# FTDI_Basic-5V.net
KiCad netlist of a schematic drawn in EAGLE
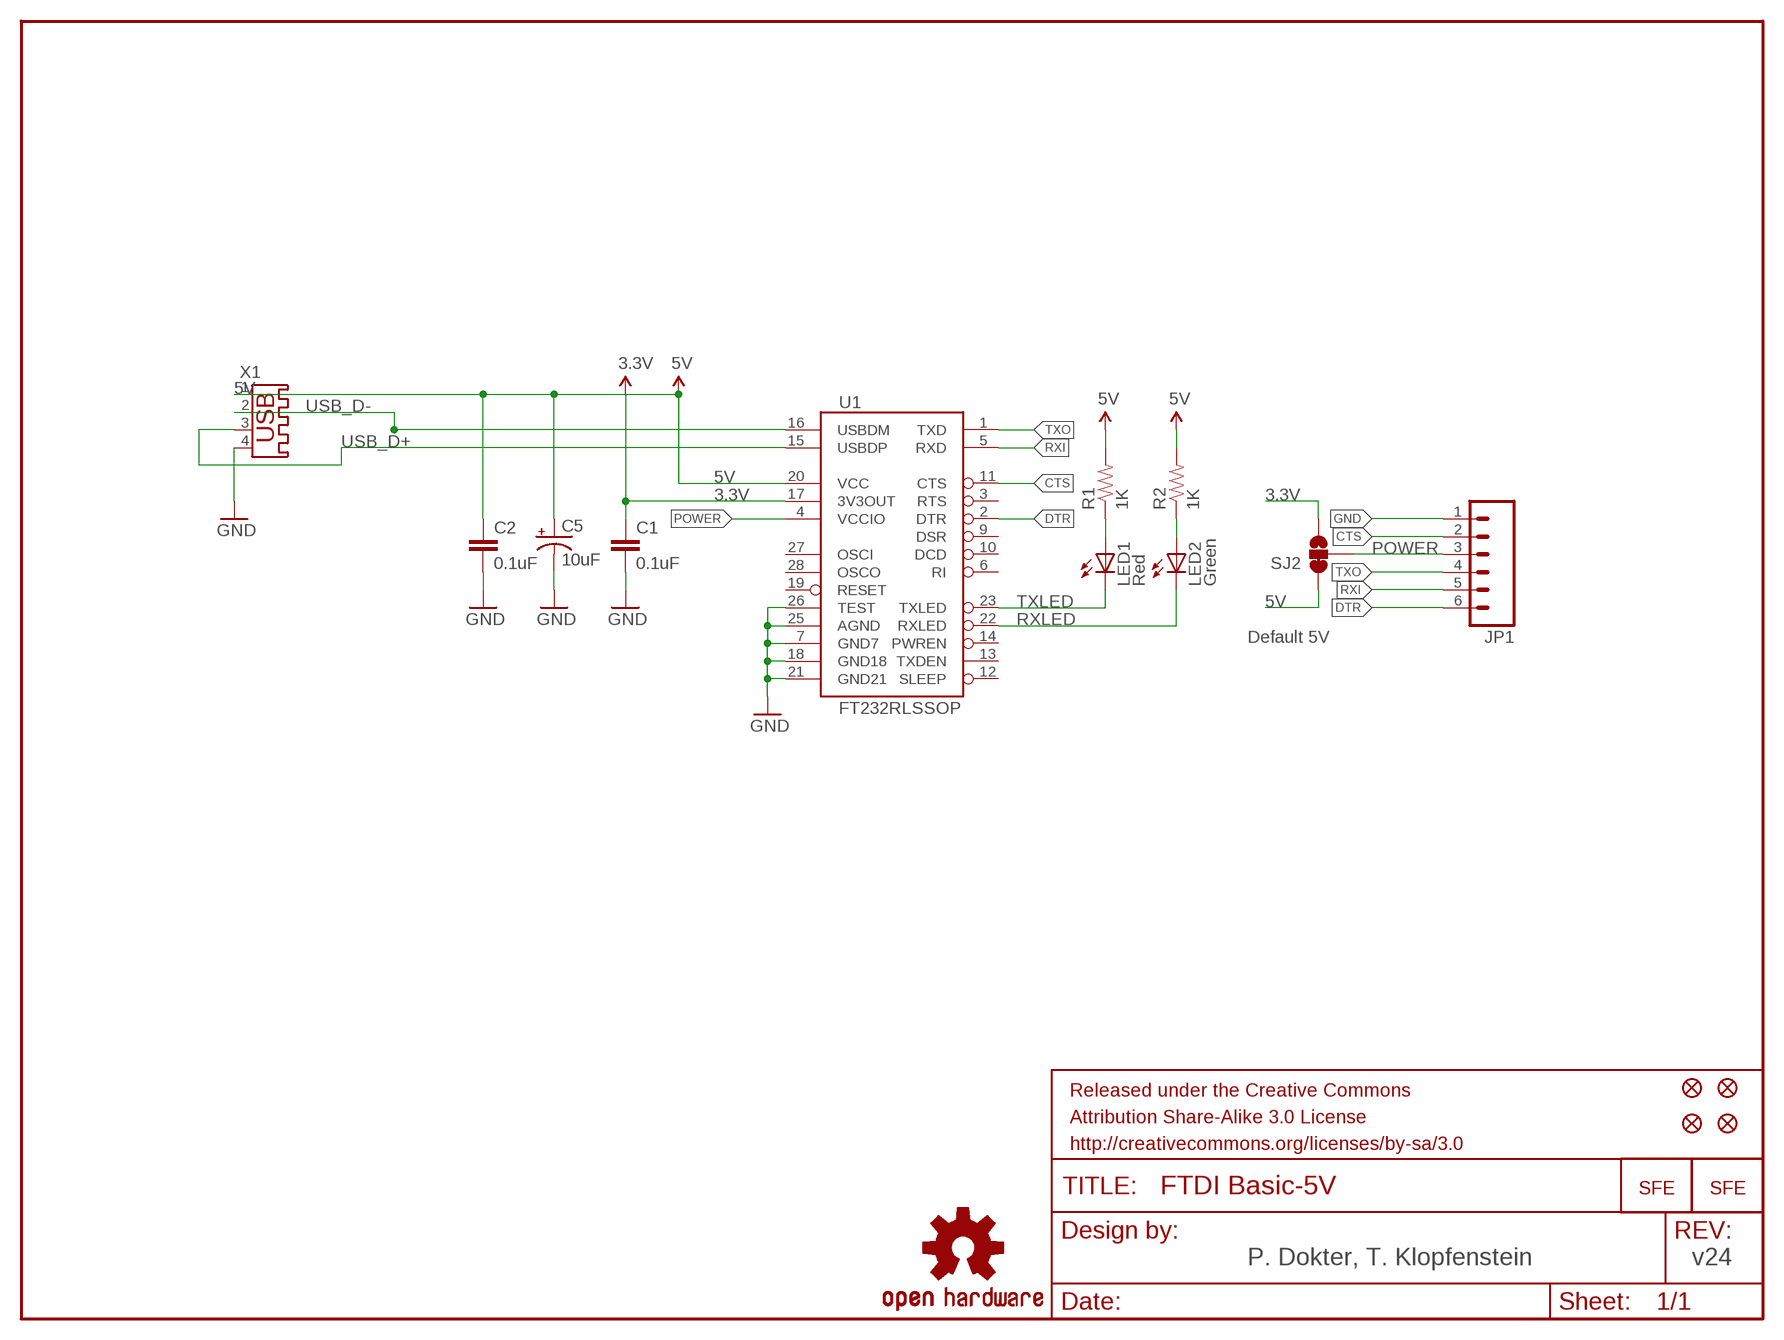
[diagram p0: schematic, sheet 1]

(export (version "E")
  (design (tool "Eeschema 10.0.6"))
  (components
    (comp (ref "C1")
      (value "0.1uF")
      (footprint "eagle-import:0603-CAP")
      (libsource (lib "eagle-import") (part "CAP0603-CAP"))
    )
    (comp (ref "C2")
      (value "0.1uF")
      (footprint "eagle-import:0603-CAP")
      (libsource (lib "eagle-import") (part "CAP0603-CAP"))
    )
    (comp (ref "C5")
      (value "10uF")
      (footprint "eagle-import:EIA3216")
      (libsource (lib "eagle-import") (part "CAP_POL1206"))
    )
    (comp (ref "FRAME1")
      (value "FRAME-LETTER")
      (footprint "eagle-import:CREATIVE_COMMONS")
      (libsource (lib "eagle-import") (part "FRAME-LETTER"))
    )
    (comp (ref "JP1")
      (value "M06SMD-FEMALE-V2")
      (footprint "eagle-import:1X06-SMD-FEMALE-V2")
      (libsource (lib "eagle-import") (part "M06SMD-FEMALE-V2"))
    )
    (comp (ref "JP2")
      (value "LOGO-SFESK")
      (footprint "eagle-import:SFE-LOGO-FLAME")
      (libsource (lib "eagle-import") (part "LOGO-SFESK"))
    )
    (comp (ref "JP3")
      (value "FIDUCIAL1X2")
      (footprint "eagle-import:FIDUCIAL-1X2")
      (libsource (lib "eagle-import") (part "FIDUCIAL1X2"))
    )
    (comp (ref "JP4")
      (value "FIDUCIAL1X2")
      (footprint "eagle-import:FIDUCIAL-1X2")
      (libsource (lib "eagle-import") (part "FIDUCIAL1X2"))
    )
    (comp (ref "JP5")
      (value "FIDUCIAL1X2")
      (footprint "eagle-import:FIDUCIAL-1X2")
      (libsource (lib "eagle-import") (part "FIDUCIAL1X2"))
    )
    (comp (ref "JP6")
      (value "FIDUCIAL1X2")
      (footprint "eagle-import:FIDUCIAL-1X2")
      (libsource (lib "eagle-import") (part "FIDUCIAL1X2"))
    )
    (comp (ref "LED1")
      (value "Red")
      (footprint "eagle-import:LED-0603")
      (libsource (lib "eagle-import") (part "LED0603"))
    )
    (comp (ref "LED2")
      (value "Green")
      (footprint "eagle-import:LED-0603")
      (libsource (lib "eagle-import") (part "LED0603"))
    )
    (comp (ref "LOGO1")
      (value "OSHW-LOGOS")
      (footprint "eagle-import:OSHW-LOGO-S")
      (libsource (lib "eagle-import") (part "OSHW-LOGOS"))
    )
    (comp (ref "R1")
      (value "1K")
      (footprint "eagle-import:0603-RES")
      (libsource (lib "eagle-import") (part "RESISTOR0603-RES"))
    )
    (comp (ref "R2")
      (value "1K")
      (footprint "eagle-import:0603-RES")
      (libsource (lib "eagle-import") (part "RESISTOR0603-RES"))
    )
    (comp (ref "SJ2")
      (value "SOLDERJUMPER_2WAYS")
      (footprint "eagle-import:SJ_3")
      (libsource (lib "eagle-import") (part "SOLDERJUMPER_2WAYS"))
    )
    (comp (ref "U$2")
      (value "LOGO-SFENW2")
      (footprint "eagle-import:SFE-NEW-WEB")
      (libsource (lib "eagle-import") (part "LOGO-SFENW2"))
    )
    (comp (ref "U1")
      (value "FT232RLSSOP")
      (footprint "eagle-import:SSOP28DB")
      (libsource (lib "eagle-import") (part "FT232RLSSOP"))
    )
    (comp (ref "X1")
      (value "USB-A003")
      (footprint "eagle-import:USB-A003")
      (libsource (lib "eagle-import") (part "USB-A003"))
    )
  )
  (nets
    (net (code "1") (name "/RXLED") (class "Default")
      (node (ref "LED2") (pin "C") (pinfunction "C_C") (pintype "passive"))
      (node (ref "U1") (pin "22") (pinfunction "RXLED_22") (pintype "input"))
    )
    (net (code "2") (name "/TXLED") (class "Default")
      (node (ref "LED1") (pin "C") (pinfunction "C_C") (pintype "passive"))
      (node (ref "U1") (pin "23") (pinfunction "TXLED_23") (pintype "input"))
    )
    (net (code "3") (name "/USB_D+") (class "Default")
      (node (ref "U1") (pin "15") (pinfunction "USBDP_15") (pintype "bidirectional"))
      (node (ref "X1") (pin "3") (pinfunction "3_3") (pintype "passive"))
    )
    (net (code "4") (name "/USB_D-") (class "Default")
      (node (ref "U1") (pin "16") (pinfunction "USBDM_16") (pintype "bidirectional"))
      (node (ref "X1") (pin "2") (pinfunction "2_2") (pintype "passive"))
    )
    (net (code "5") (name "3.3V") (class "Default")
      (node (ref "C1") (pin "1") (pinfunction "1_1") (pintype "passive"))
      (node (ref "SJ2") (pin "3") (pinfunction "3_3") (pintype "passive"))
      (node (ref "U1") (pin "17") (pinfunction "3V3OUT_17") (pintype "output"))
    )
    (net (code "6") (name "5V") (class "Default")
      (node (ref "C2") (pin "1") (pinfunction "1_1") (pintype "passive"))
      (node (ref "C5") (pin "A") (pinfunction "+_A") (pintype "passive"))
      (node (ref "R1") (pin "2") (pinfunction "2_2") (pintype "passive"))
      (node (ref "R2") (pin "2") (pinfunction "2_2") (pintype "passive"))
      (node (ref "SJ2") (pin "1") (pinfunction "1_1") (pintype "passive"))
      (node (ref "U1") (pin "20") (pinfunction "VCC_20") (pintype "power_in"))
      (node (ref "X1") (pin "1") (pinfunction "1_1") (pintype "passive"))
    )
    (net (code "7") (name "CTS") (class "Default")
      (node (ref "JP1") (pin "2") (pinfunction "2_2") (pintype "passive"))
      (node (ref "U1") (pin "11") (pinfunction "CTS_11") (pintype "input"))
    )
    (net (code "8") (name "DTR") (class "Default")
      (node (ref "JP1") (pin "6") (pinfunction "6_6") (pintype "passive"))
      (node (ref "U1") (pin "2") (pinfunction "DTR_2") (pintype "output"))
    )
    (net (code "9") (name "GND") (class "Default")
      (node (ref "C1") (pin "2") (pinfunction "2_2") (pintype "passive"))
      (node (ref "C2") (pin "2") (pinfunction "2_2") (pintype "passive"))
      (node (ref "C5") (pin "C") (pinfunction "-_C") (pintype "passive"))
      (node (ref "JP1") (pin "1") (pinfunction "1_1") (pintype "passive"))
      (node (ref "U1") (pin "18") (pinfunction "GND18_18") (pintype "power_in"))
      (node (ref "U1") (pin "21") (pinfunction "GND21_21") (pintype "power_in"))
      (node (ref "U1") (pin "25") (pinfunction "AGND_25") (pintype "power_in"))
      (node (ref "U1") (pin "26") (pinfunction "TEST_26") (pintype "input"))
      (node (ref "U1") (pin "7") (pinfunction "GND7_7") (pintype "power_in"))
      (node (ref "X1") (pin "4") (pinfunction "4_4") (pintype "passive"))
    )
    (net (code "10") (name "Net-(LED1-PadA)") (class "Default")
      (node (ref "LED1") (pin "A") (pinfunction "A_A") (pintype "passive"))
      (node (ref "R1") (pin "1") (pinfunction "1_1") (pintype "passive"))
    )
    (net (code "11") (name "Net-(LED2-PadA)") (class "Default")
      (node (ref "LED2") (pin "A") (pinfunction "A_A") (pintype "passive"))
      (node (ref "R2") (pin "1") (pinfunction "1_1") (pintype "passive"))
    )
    (net (code "12") (name "POWER") (class "Default")
      (node (ref "JP1") (pin "3") (pinfunction "3_3") (pintype "passive"))
      (node (ref "SJ2") (pin "2") (pinfunction "2_2") (pintype "passive"))
      (node (ref "U1") (pin "4") (pinfunction "VCCIO_4") (pintype "power_in"))
    )
    (net (code "13") (name "RXI") (class "Default")
      (node (ref "JP1") (pin "5") (pinfunction "5_5") (pintype "passive"))
      (node (ref "U1") (pin "5") (pinfunction "RXD_5") (pintype "input"))
    )
    (net (code "14") (name "TXO") (class "Default")
      (node (ref "JP1") (pin "4") (pinfunction "4_4") (pintype "passive"))
      (node (ref "U1") (pin "1") (pinfunction "TXD_1") (pintype "output"))
    )
    (net (code "15") (name "unconnected-(U1-DCD-Pad10)") (class "Default")
      (node (ref "U1") (pin "10") (pinfunction "DCD_10") (pintype "input"))
    )
    (net (code "16") (name "unconnected-(U1-DSR-Pad9)") (class "Default")
      (node (ref "U1") (pin "9") (pinfunction "DSR_9") (pintype "input"))
    )
    (net (code "17") (name "unconnected-(U1-OSCI-Pad27)") (class "Default")
      (node (ref "U1") (pin "27") (pinfunction "OSCI_27") (pintype "input"))
    )
    (net (code "18") (name "unconnected-(U1-OSCO-Pad28)") (class "Default")
      (node (ref "U1") (pin "28") (pinfunction "OSCO_28") (pintype "output"))
    )
    (net (code "19") (name "unconnected-(U1-PWREN-Pad14)") (class "Default")
      (node (ref "U1") (pin "14") (pinfunction "PWREN_14") (pintype "input"))
    )
    (net (code "20") (name "unconnected-(U1-RESET-Pad19)") (class "Default")
      (node (ref "U1") (pin "19") (pinfunction "RESET_19") (pintype "input"))
    )
    (net (code "21") (name "unconnected-(U1-RI-Pad6)") (class "Default")
      (node (ref "U1") (pin "6") (pinfunction "RI_6") (pintype "input"))
    )
    (net (code "22") (name "unconnected-(U1-RTS-Pad3)") (class "Default")
      (node (ref "U1") (pin "3") (pinfunction "RTS_3") (pintype "output"))
    )
    (net (code "23") (name "unconnected-(U1-SLEEP-Pad12)") (class "Default")
      (node (ref "U1") (pin "12") (pinfunction "SLEEP_12") (pintype "input"))
    )
    (net (code "24") (name "unconnected-(U1-TXDEN-Pad13)") (class "Default")
      (node (ref "U1") (pin "13") (pinfunction "TXDEN_13") (pintype "input"))
    )
  )
)
